# LowduinoSMD_Take3.net
KiCad netlist of a schematic drawn in EAGLE
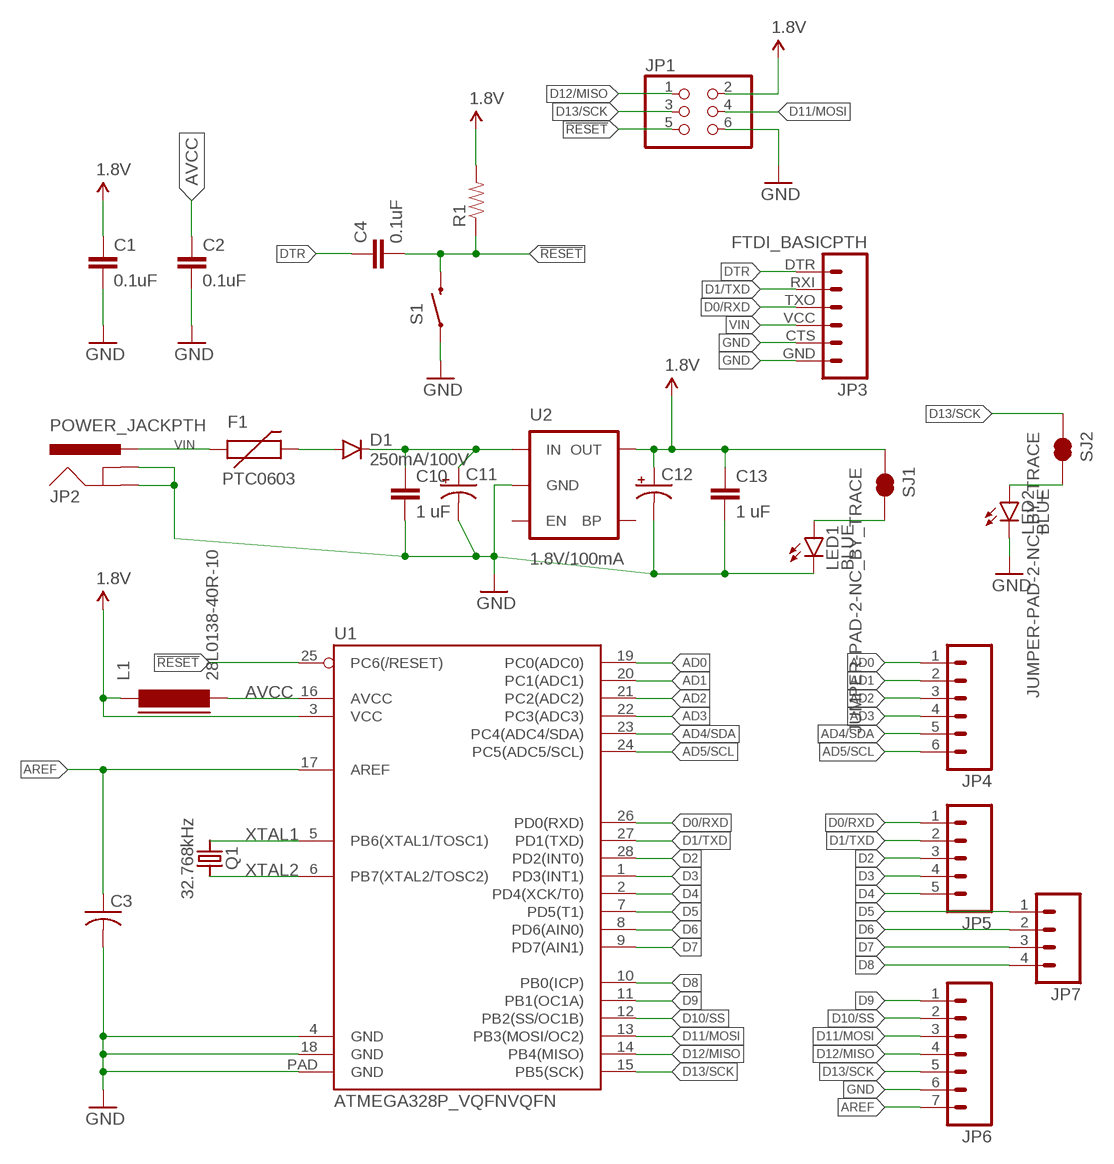
[diagram p0: schematic, sheet 1]

(export (version "E")
  (design (tool "Eeschema 10.0.6"))
  (components
    (comp (ref "C1")
      (value "0.1uF")
      (footprint "eagle-import:0603-CAP")
      (libsource (lib "eagle-import") (part "CAP0603-CAP"))
    )
    (comp (ref "C2")
      (value "0.1uF")
      (footprint "eagle-import:0603-CAP")
      (libsource (lib "eagle-import") (part "CAP0603-CAP"))
    )
    (comp (ref "C3")
      (value "C-US01005")
      (footprint "eagle-import:C01005")
      (libsource (lib "eagle-import") (part "C-US01005"))
    )
    (comp (ref "C4")
      (value "0.1uF")
      (footprint "eagle-import:0402-CAP")
      (libsource (lib "eagle-import") (part "CAP0402-CAP"))
    )
    (comp (ref "C10")
      (value "1 uF")
      (footprint "eagle-import:0402-CAP")
      (libsource (lib "eagle-import") (part "CAP0402-CAP"))
    )
    (comp (ref "C11")
      (value "CAP_POLC")
      (footprint "eagle-import:PANASONIC_C")
      (libsource (lib "eagle-import") (part "CAP_POLC"))
    )
    (comp (ref "C12")
      (value "CAP_POLC")
      (footprint "eagle-import:PANASONIC_C")
      (libsource (lib "eagle-import") (part "CAP_POLC"))
    )
    (comp (ref "C13")
      (value "1 uF")
      (footprint "eagle-import:0402-CAP")
      (libsource (lib "eagle-import") (part "CAP0402-CAP"))
    )
    (comp (ref "D1")
      (value "250mA/100V")
      (footprint "eagle-import:SOD-323")
      (libsource (lib "eagle-import") (part "DIODEBAS16"))
    )
    (comp (ref "F1")
      (value "PTC0603")
      (footprint "eagle-import:0603")
      (libsource (lib "eagle-import") (part "PTC0603"))
    )
    (comp (ref "JP1")
      (value "PINHD-2X3")
      (footprint "eagle-import:2X03")
      (libsource (lib "eagle-import") (part "PINHD-2X3"))
    )
    (comp (ref "JP2")
      (value "POWER_JACKPTH")
      (footprint "eagle-import:POWER_JACK_PTH")
      (libsource (lib "eagle-import") (part "POWER_JACKPTH"))
    )
    (comp (ref "JP3")
      (value "FTDI_BASICPTH")
      (footprint "eagle-import:FTDI_BASIC")
      (libsource (lib "eagle-import") (part "FTDI_BASICPTH"))
    )
    (comp (ref "JP4")
      (value "M06SILK_FEMALE_PTH")
      (footprint "eagle-import:1X06")
      (libsource (lib "eagle-import") (part "M06SILK_FEMALE_PTH"))
    )
    (comp (ref "JP5")
      (value "M05PTH")
      (footprint "eagle-import:1X05")
      (libsource (lib "eagle-import") (part "M05PTH"))
    )
    (comp (ref "JP6")
      (value "M07")
      (footprint "eagle-import:1X07")
      (libsource (lib "eagle-import") (part "M07"))
    )
    (comp (ref "JP7")
      (value "M04PTH")
      (footprint "eagle-import:1X04")
      (libsource (lib "eagle-import") (part "M04PTH"))
    )
    (comp (ref "L1")
      (value "28L0138-40R-10")
      (footprint "eagle-import:FB402")
      (libsource (lib "eagle-import") (part "FERRITE-0402"))
    )
    (comp (ref "LED1")
      (value "BLUE")
      (footprint "eagle-import:LED-0603")
      (libsource (lib "eagle-import") (part "LED-BLUE0603"))
    )
    (comp (ref "LED2")
      (value "BLUE")
      (footprint "eagle-import:LED-0603")
      (libsource (lib "eagle-import") (part "LED-BLUE0603"))
    )
    (comp (ref "Q1")
      (value "32.768kHz")
      (footprint "eagle-import:2-SMD")
      (libsource (lib "eagle-import") (part "FX12232.768KHZ"))
    )
    (comp (ref "R1")
      (value "RESISTOR0402")
      (footprint "eagle-import:0402-RES")
      (libsource (lib "eagle-import") (part "RESISTOR0402"))
    )
    (comp (ref "S1")
      (value "SWITCH-MOMENTARY-2SMD")
      (footprint "eagle-import:TACTILE-SWITCH-SMD")
      (libsource (lib "eagle-import") (part "SWITCH-MOMENTARY-2SMD"))
    )
    (comp (ref "SJ1")
      (value "JUMPER-PAD-2-NC_BY_TRACE")
      (footprint "eagle-import:PAD-JUMPER-2-NC_BY_TRACE_YES_SILK")
      (libsource (lib "eagle-import") (part "JUMPER-PAD-2-NC_BY_TRACE"))
    )
    (comp (ref "SJ2")
      (value "JUMPER-PAD-2-NC_BY_TRACE")
      (footprint "eagle-import:PAD-JUMPER-2-NC_BY_TRACE_YES_SILK")
      (libsource (lib "eagle-import") (part "JUMPER-PAD-2-NC_BY_TRACE"))
    )
    (comp (ref "U1")
      (value "ATMEGA328P_VQFNVQFN")
      (footprint "eagle-import:VQFN-28")
      (libsource (lib "eagle-import") (part "ATMEGA328P_VQFNVQFN"))
    )
    (comp (ref "U2")
      (value "1.8V/100mA")
      (footprint "eagle-import:SC70")
      (libsource (lib "eagle-import") (part "V_REG_SP62141.8V"))
    )
  )
  (nets
    (net (code "1") (name "/XTAL1") (class "Default")
      (node (ref "Q1") (pin "1") (pinfunction "1_1") (pintype "passive"))
      (node (ref "U1") (pin "5") (pinfunction "PB6(XTAL1/TOSC1)_5") (pintype "bidirectional"))
    )
    (net (code "2") (name "/XTAL2") (class "Default")
      (node (ref "Q1") (pin "2") (pinfunction "2_2") (pintype "passive"))
      (node (ref "U1") (pin "6") (pinfunction "PB7(XTAL2/TOSC2)_6") (pintype "bidirectional"))
    )
    (net (code "3") (name "/~{RESET}") (class "Default")
      (node (ref "C4") (pin "2") (pinfunction "2_2") (pintype "passive"))
      (node (ref "JP1") (pin "5") (pinfunction "5_5") (pintype "passive"))
      (node (ref "R1") (pin "1") (pinfunction "1_1") (pintype "passive"))
      (node (ref "S1") (pin "3") (pinfunction "2_3") (pintype "passive"))
      (node (ref "U1") (pin "25") (pinfunction "PC6(/RESET)_25") (pintype "bidirectional"))
    )
    (net (code "4") (name "1.8V") (class "Default")
      (node (ref "C1") (pin "1") (pinfunction "1_1") (pintype "passive"))
      (node (ref "C12") (pin "+") (pinfunction "+_+") (pintype "passive"))
      (node (ref "C13") (pin "1") (pinfunction "1_1") (pintype "passive"))
      (node (ref "JP1") (pin "2") (pinfunction "2_2") (pintype "passive"))
      (node (ref "L1") (pin "1") (pinfunction "1_1") (pintype "passive"))
      (node (ref "R1") (pin "2") (pinfunction "2_2") (pintype "passive"))
      (node (ref "SJ1") (pin "1") (pinfunction "1_1") (pintype "passive"))
      (node (ref "U1") (pin "3") (pinfunction "VCC_3") (pintype "bidirectional"))
      (node (ref "U2") (pin "5") (pinfunction "OUT_5") (pintype "passive"))
    )
    (net (code "5") (name "AD0") (class "Default")
      (node (ref "JP4") (pin "1") (pinfunction "1_1") (pintype "passive"))
      (node (ref "U1") (pin "19") (pinfunction "PC0(ADC0)_19") (pintype "bidirectional"))
    )
    (net (code "6") (name "AD1") (class "Default")
      (node (ref "JP4") (pin "2") (pinfunction "2_2") (pintype "passive"))
      (node (ref "U1") (pin "20") (pinfunction "PC1(ADC1)_20") (pintype "bidirectional"))
    )
    (net (code "7") (name "AD2") (class "Default")
      (node (ref "JP4") (pin "3") (pinfunction "3_3") (pintype "passive"))
      (node (ref "U1") (pin "21") (pinfunction "PC2(ADC2)_21") (pintype "bidirectional"))
    )
    (net (code "8") (name "AD3") (class "Default")
      (node (ref "JP4") (pin "4") (pinfunction "4_4") (pintype "passive"))
      (node (ref "U1") (pin "22") (pinfunction "PC3(ADC3)_22") (pintype "bidirectional"))
    )
    (net (code "9") (name "AD4{slash}SDA") (class "Default")
      (node (ref "JP4") (pin "5") (pinfunction "5_5") (pintype "passive"))
      (node (ref "U1") (pin "23") (pinfunction "PC4(ADC4/SDA)_23") (pintype "bidirectional"))
    )
    (net (code "10") (name "AD5{slash}SCL") (class "Default")
      (node (ref "JP4") (pin "6") (pinfunction "6_6") (pintype "passive"))
      (node (ref "U1") (pin "24") (pinfunction "PC5(ADC5/SCL)_24") (pintype "bidirectional"))
    )
    (net (code "11") (name "AREF") (class "Default")
      (node (ref "C3") (pin "1") (pinfunction "1_1") (pintype "passive"))
      (node (ref "JP6") (pin "7") (pinfunction "7_7") (pintype "passive"))
      (node (ref "U1") (pin "17") (pinfunction "AREF_17") (pintype "bidirectional"))
    )
    (net (code "12") (name "AVCC") (class "Default")
      (node (ref "C2") (pin "1") (pinfunction "1_1") (pintype "passive"))
      (node (ref "L1") (pin "2") (pinfunction "2_2") (pintype "passive"))
      (node (ref "U1") (pin "16") (pinfunction "AVCC_16") (pintype "bidirectional"))
    )
    (net (code "13") (name "D0{slash}RXD") (class "Default")
      (node (ref "JP3") (pin "TXO") (pinfunction "3_TXO") (pintype "passive"))
      (node (ref "JP5") (pin "1") (pinfunction "1_1") (pintype "passive"))
      (node (ref "U1") (pin "26") (pinfunction "PD0(RXD)_26") (pintype "bidirectional"))
    )
    (net (code "14") (name "D1{slash}TXD") (class "Default")
      (node (ref "JP3") (pin "RXI") (pinfunction "2_RXI") (pintype "passive"))
      (node (ref "JP5") (pin "2") (pinfunction "2_2") (pintype "passive"))
      (node (ref "U1") (pin "27") (pinfunction "PD1(TXD)_27") (pintype "bidirectional"))
    )
    (net (code "15") (name "D2") (class "Default")
      (node (ref "JP5") (pin "3") (pinfunction "3_3") (pintype "passive"))
      (node (ref "U1") (pin "28") (pinfunction "PD2(INT0)_28") (pintype "bidirectional"))
    )
    (net (code "16") (name "D3") (class "Default")
      (node (ref "JP5") (pin "4") (pinfunction "4_4") (pintype "passive"))
      (node (ref "U1") (pin "1") (pinfunction "PD3(INT1)_1") (pintype "bidirectional"))
    )
    (net (code "17") (name "D4") (class "Default")
      (node (ref "JP5") (pin "5") (pinfunction "5_5") (pintype "passive"))
      (node (ref "U1") (pin "2") (pinfunction "PD4(XCK/T0)_2") (pintype "bidirectional"))
    )
    (net (code "18") (name "D5") (class "Default")
      (node (ref "JP7") (pin "1") (pinfunction "1_1") (pintype "passive"))
      (node (ref "U1") (pin "7") (pinfunction "PD5(T1)_7") (pintype "bidirectional"))
    )
    (net (code "19") (name "D6") (class "Default")
      (node (ref "JP7") (pin "2") (pinfunction "2_2") (pintype "passive"))
      (node (ref "U1") (pin "8") (pinfunction "PD6(AIN0)_8") (pintype "bidirectional"))
    )
    (net (code "20") (name "D7") (class "Default")
      (node (ref "JP7") (pin "3") (pinfunction "3_3") (pintype "passive"))
      (node (ref "U1") (pin "9") (pinfunction "PD7(AIN1)_9") (pintype "bidirectional"))
    )
    (net (code "21") (name "D8") (class "Default")
      (node (ref "JP7") (pin "4") (pinfunction "4_4") (pintype "passive"))
      (node (ref "U1") (pin "10") (pinfunction "PB0(ICP)_10") (pintype "bidirectional"))
    )
    (net (code "22") (name "D9") (class "Default")
      (node (ref "JP6") (pin "1") (pinfunction "1_1") (pintype "passive"))
      (node (ref "U1") (pin "11") (pinfunction "PB1(OC1A)_11") (pintype "bidirectional"))
    )
    (net (code "23") (name "D10{slash}SS") (class "Default")
      (node (ref "JP6") (pin "2") (pinfunction "2_2") (pintype "passive"))
      (node (ref "U1") (pin "12") (pinfunction "PB2(SS/OC1B)_12") (pintype "bidirectional"))
    )
    (net (code "24") (name "D11{slash}MOSI") (class "Default")
      (node (ref "JP1") (pin "4") (pinfunction "4_4") (pintype "passive"))
      (node (ref "JP6") (pin "3") (pinfunction "3_3") (pintype "passive"))
      (node (ref "U1") (pin "13") (pinfunction "PB3(MOSI/OC2)_13") (pintype "bidirectional"))
    )
    (net (code "25") (name "D12{slash}MISO") (class "Default")
      (node (ref "JP1") (pin "1") (pinfunction "1_1") (pintype "passive"))
      (node (ref "JP6") (pin "4") (pinfunction "4_4") (pintype "passive"))
      (node (ref "U1") (pin "14") (pinfunction "PB4(MISO)_14") (pintype "bidirectional"))
    )
    (net (code "26") (name "D13{slash}SCK") (class "Default")
      (node (ref "JP1") (pin "3") (pinfunction "3_3") (pintype "passive"))
      (node (ref "JP6") (pin "5") (pinfunction "5_5") (pintype "passive"))
      (node (ref "SJ2") (pin "1") (pinfunction "1_1") (pintype "passive"))
      (node (ref "U1") (pin "15") (pinfunction "PB5(SCK)_15") (pintype "bidirectional"))
    )
    (net (code "27") (name "DTR") (class "Default")
      (node (ref "C4") (pin "1") (pinfunction "1_1") (pintype "passive"))
      (node (ref "JP3") (pin "DTR") (pinfunction "1_DTR") (pintype "passive"))
    )
    (net (code "28") (name "GND") (class "Default")
      (node (ref "C1") (pin "2") (pinfunction "2_2") (pintype "passive"))
      (node (ref "C10") (pin "2") (pinfunction "2_2") (pintype "passive"))
      (node (ref "C11") (pin "-") (pinfunction "-_-") (pintype "passive"))
      (node (ref "C12") (pin "-") (pinfunction "-_-") (pintype "passive"))
      (node (ref "C13") (pin "2") (pinfunction "2_2") (pintype "passive"))
      (node (ref "C2") (pin "2") (pinfunction "2_2") (pintype "passive"))
      (node (ref "C3") (pin "2") (pinfunction "2_2") (pintype "passive"))
      (node (ref "JP1") (pin "6") (pinfunction "6_6") (pintype "passive"))
      (node (ref "JP2") (pin "GND") (pinfunction "GND_GND") (pintype "bidirectional"))
      (node (ref "JP2") (pin "GNDBREAK") (pinfunction "GNDBREAK_GNDBREAK") (pintype "bidirectional"))
      (node (ref "JP3") (pin "CTS") (pinfunction "5_CTS") (pintype "passive"))
      (node (ref "JP3") (pin "GND") (pinfunction "6_GND") (pintype "passive"))
      (node (ref "JP6") (pin "6") (pinfunction "6_6") (pintype "passive"))
      (node (ref "LED1") (pin "C") (pinfunction "C_C") (pintype "passive"))
      (node (ref "LED2") (pin "C") (pinfunction "C_C") (pintype "passive"))
      (node (ref "S1") (pin "1") (pinfunction "1_1") (pintype "passive"))
      (node (ref "U1") (pin "18") (pinfunction "GND_18") (pintype "bidirectional"))
      (node (ref "U1") (pin "4") (pinfunction "GND_4") (pintype "bidirectional"))
      (node (ref "U1") (pin "PAD") (pinfunction "GND_PAD") (pintype "bidirectional"))
      (node (ref "U2") (pin "2") (pinfunction "GND_2") (pintype "input"))
    )
    (net (code "29") (name "Net-(D1-PadA)") (class "Default")
      (node (ref "D1") (pin "A") (pinfunction "A_A") (pintype "passive"))
      (node (ref "F1") (pin "2") (pinfunction "2_2") (pintype "bidirectional"))
    )
    (net (code "30") (name "Net-(LED1-PadA)") (class "Default")
      (node (ref "LED1") (pin "A") (pinfunction "A_A") (pintype "passive"))
      (node (ref "SJ1") (pin "2") (pinfunction "2_2") (pintype "passive"))
    )
    (net (code "31") (name "Net-(LED2-PadA)") (class "Default")
      (node (ref "LED2") (pin "A") (pinfunction "A_A") (pintype "passive"))
      (node (ref "SJ2") (pin "2") (pinfunction "2_2") (pintype "passive"))
    )
    (net (code "32") (name "Net-(U2-IN)") (class "Default")
      (node (ref "C10") (pin "1") (pinfunction "1_1") (pintype "passive"))
      (node (ref "C11") (pin "+") (pinfunction "+_+") (pintype "passive"))
      (node (ref "D1") (pin "C") (pinfunction "C_C") (pintype "passive"))
      (node (ref "U2") (pin "1") (pinfunction "IN_1") (pintype "input"))
    )
    (net (code "33") (name "VIN") (class "Default")
      (node (ref "F1") (pin "1") (pinfunction "1_1") (pintype "bidirectional"))
      (node (ref "JP2") (pin "PWR") (pinfunction "PWR_PWR") (pintype "bidirectional"))
      (node (ref "JP3") (pin "VCC") (pinfunction "4_VCC") (pintype "passive"))
    )
    (net (code "34") (name "unconnected-(U2-BP-Pad4)") (class "Default")
      (node (ref "U2") (pin "4") (pinfunction "BP_4") (pintype "input"))
    )
    (net (code "35") (name "unconnected-(U2-EN-Pad3)") (class "Default")
      (node (ref "U2") (pin "3") (pinfunction "EN_3") (pintype "input"))
    )
  )
)
